# 42Board.net
KiCad netlist of a schematic drawn in EAGLE
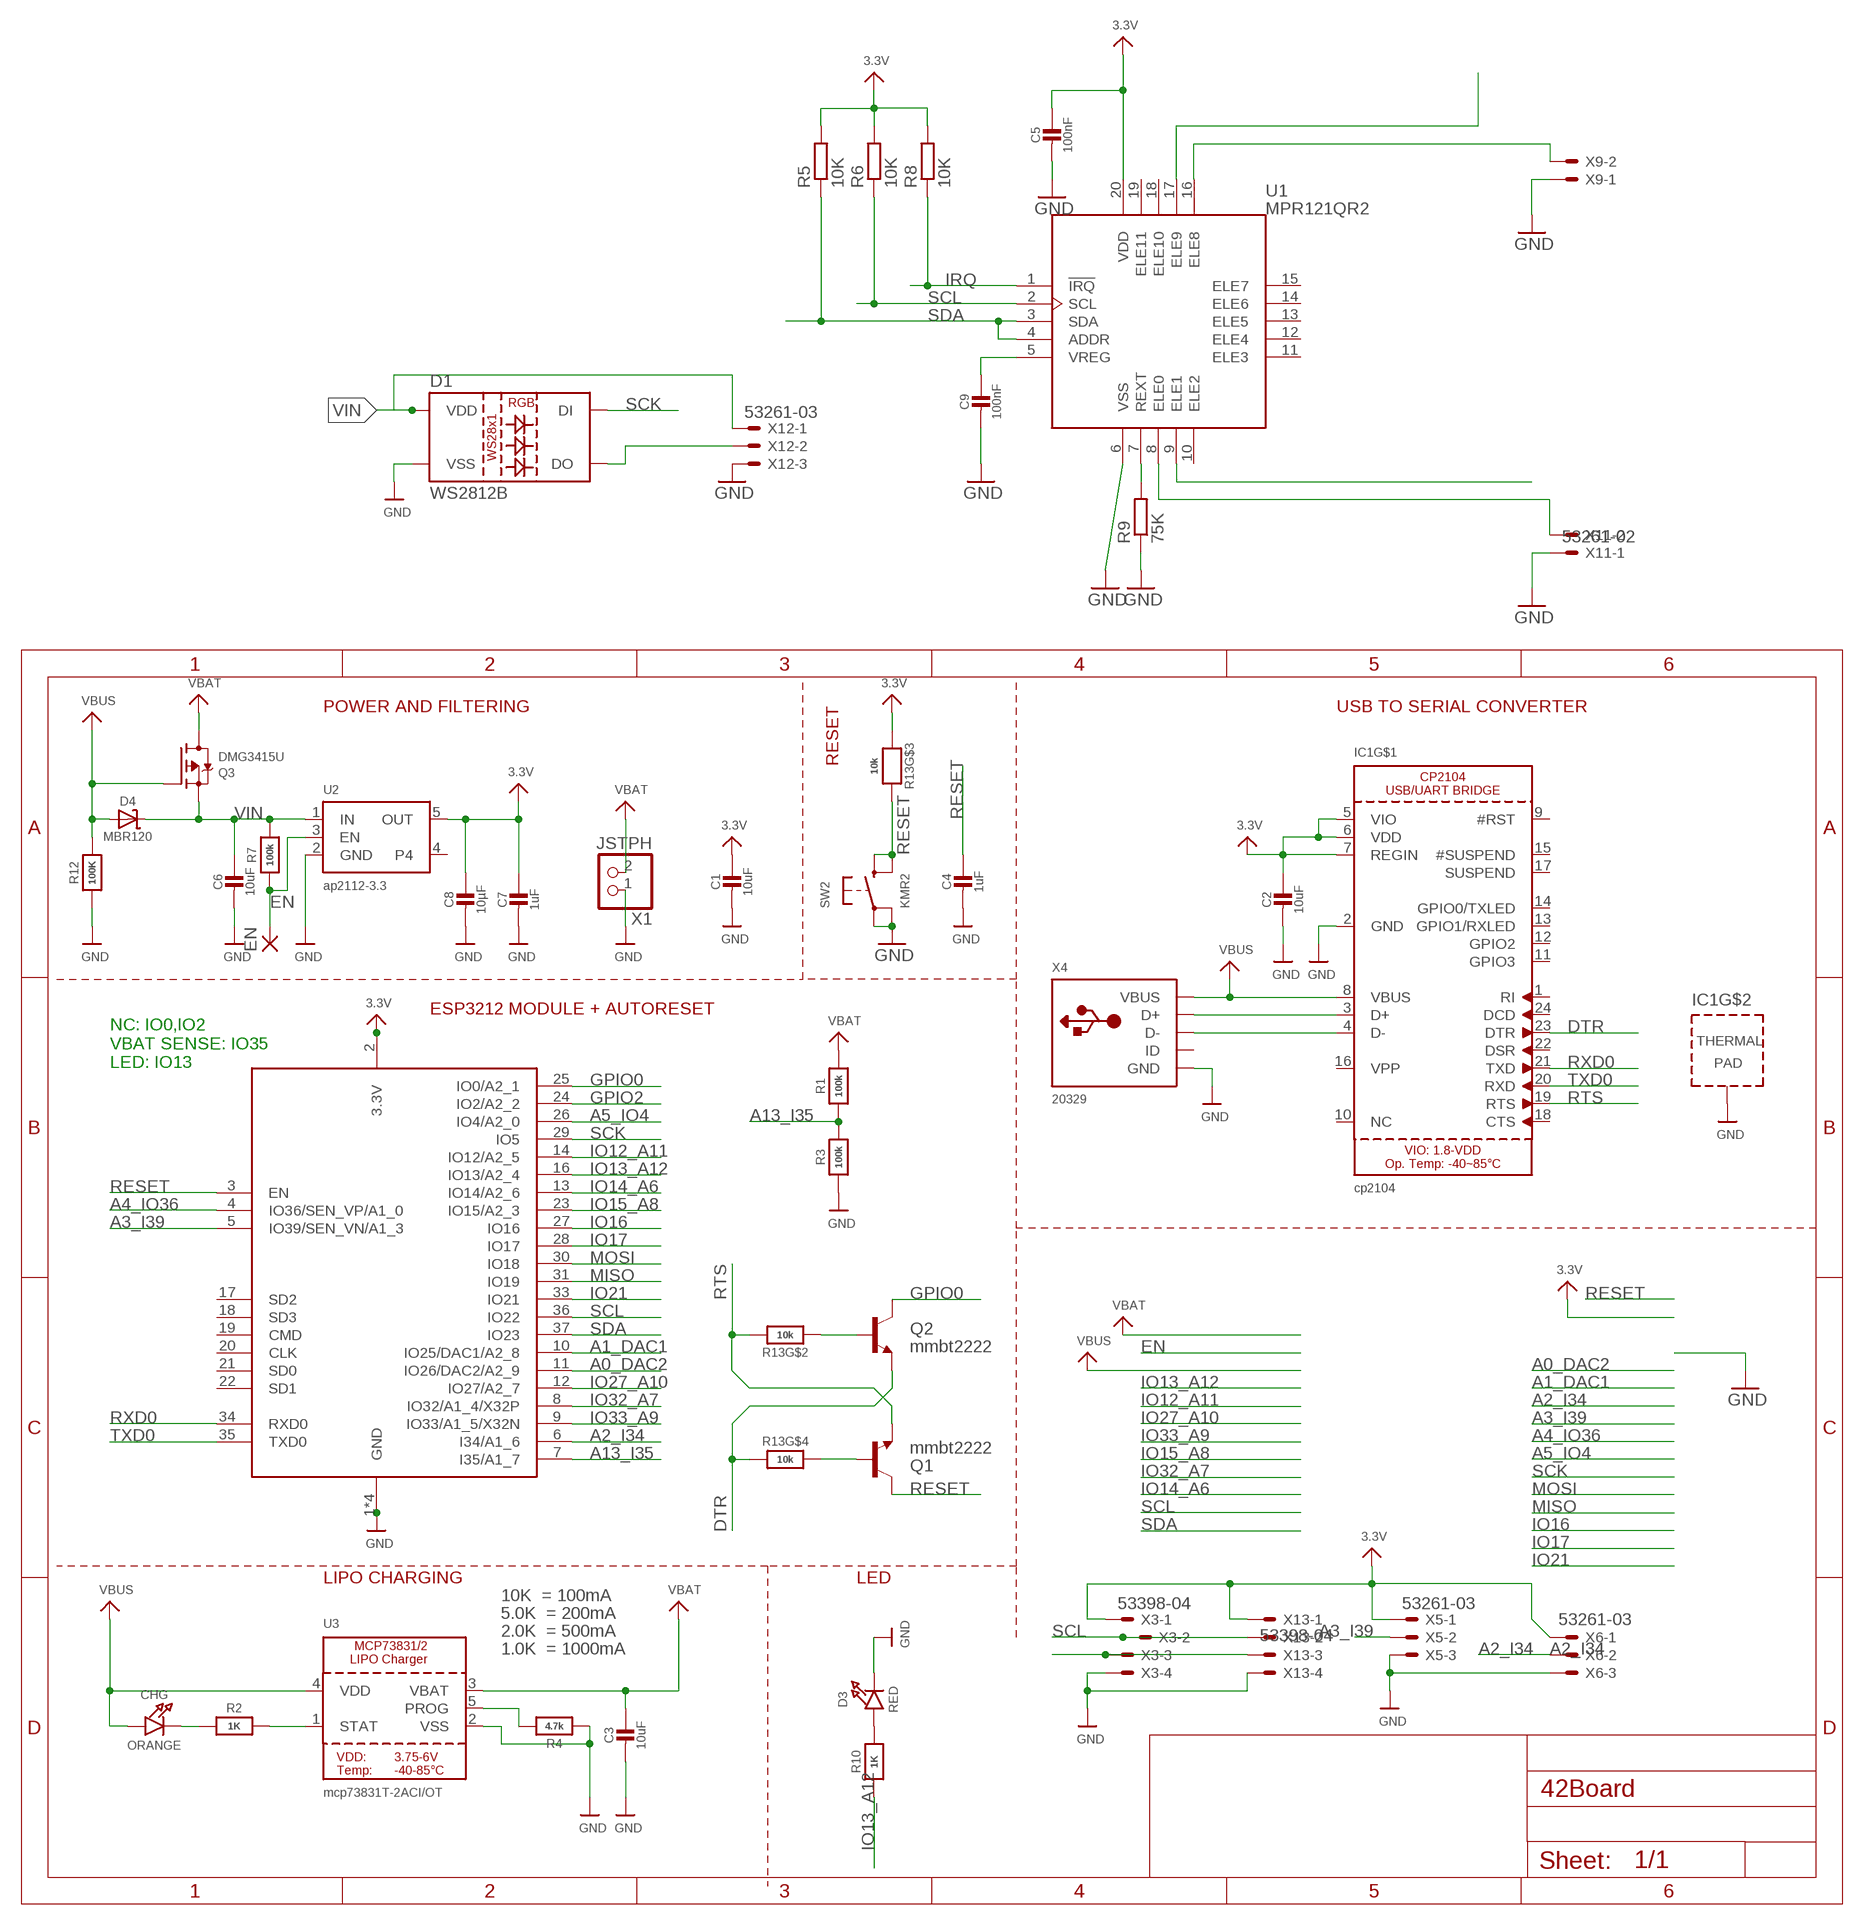
[diagram p0: schematic, sheet 1]

(export (version "E")
  (design (tool "Eeschema 10.0.6"))
  (components
    (comp (ref "C1")
      (value "10uF")
      (footprint "eagle-import:0805-NO")
      (libsource (lib "eagle-import") (part "CAP_CERAMIC0805-NOOUTLINE"))
    )
    (comp (ref "C2")
      (value "10uF")
      (footprint "eagle-import:0805-NO")
      (libsource (lib "eagle-import") (part "CAP_CERAMIC0805-NOOUTLINE"))
    )
    (comp (ref "C3")
      (value "10uF")
      (footprint "eagle-import:0805-NO")
      (libsource (lib "eagle-import") (part "CAP_CERAMIC0805-NOOUTLINE"))
    )
    (comp (ref "C4")
      (value "1uF")
      (footprint "eagle-import:0603-NO")
      (libsource (lib "eagle-import") (part "CAP_CERAMIC0603_NO"))
    )
    (comp (ref "C5")
      (value "100nF")
      (footprint "eagle-import:0603-NO")
      (libsource (lib "eagle-import") (part "CAP_CERAMIC0603_NO"))
    )
    (comp (ref "C6")
      (value "10uF")
      (footprint "eagle-import:0805-NO")
      (libsource (lib "eagle-import") (part "CAP_CERAMIC0805-NOOUTLINE"))
    )
    (comp (ref "C7")
      (value "1uF")
      (footprint "eagle-import:0603-NO")
      (libsource (lib "eagle-import") (part "CAP_CERAMIC0603_NO"))
    )
    (comp (ref "C8")
      (value "10µF")
      (footprint "eagle-import:0805-NO")
      (libsource (lib "eagle-import") (part "CAP_CERAMIC0805-NOOUTLINE"))
    )
    (comp (ref "C9")
      (value "100nF")
      (footprint "eagle-import:0603-NO")
      (libsource (lib "eagle-import") (part "CAP_CERAMIC0603_NO"))
    )
    (comp (ref "CHG")
      (value "ORANGE")
      (footprint "eagle-import:CHIPLED_0805_NOOUTLINE")
      (libsource (lib "eagle-import") (part "LED0805_NOOUTLINE"))
    )
    (comp (ref "D1")
      (value "WS2812B")
      (footprint "eagle-import:WS2812B")
      (libsource (lib "eagle-import") (part "WS2812B"))
    )
    (comp (ref "D3")
      (value "RED")
      (footprint "eagle-import:CHIPLED_0805_NOOUTLINE")
      (libsource (lib "eagle-import") (part "LED0805_NOOUTLINE"))
    )
    (comp (ref "D4")
      (value "MBR120")
      (footprint "eagle-import:SOD-123")
      (libsource (lib "eagle-import") (part "DIODE-SCHOTTKYSOD-123"))
    )
    (comp (ref "EN")
      (value "1,6/0,8")
      (footprint "eagle-import:1,6_0,8")
      (libsource (lib "eagle-import") (part "1,6/0,8"))
    )
    (comp (ref "IC1")
      (value "cp2104")
      (footprint "eagle-import:QFN24_4MM_SMSC")
      (libsource (lib "eagle-import") (part "CP2104"))
    )
    (comp (ref "Q1")
      (value "mmbt2222")
      (footprint "eagle-import:SOT23-3")
      (libsource (lib "eagle-import") (part "TRANSISTOR_NPNSOT23-3"))
    )
    (comp (ref "Q2")
      (value "mmbt2222")
      (footprint "eagle-import:SOT23-3")
      (libsource (lib "eagle-import") (part "TRANSISTOR_NPNSOT23-3"))
    )
    (comp (ref "Q3")
      (value "DMG3415U")
      (footprint "eagle-import:SOT23-R")
      (libsource (lib "eagle-import") (part "MOSFET-P"))
    )
    (comp (ref "R1")
      (value "100k")
      (footprint "eagle-import:0603-NO")
      (libsource (lib "eagle-import") (part "RESISTOR_0603_NOOUT"))
    )
    (comp (ref "R2")
      (value "1K")
      (footprint "eagle-import:0603-NO")
      (libsource (lib "eagle-import") (part "RESISTOR_0603_NOOUT"))
    )
    (comp (ref "R3")
      (value "100k")
      (footprint "eagle-import:0603-NO")
      (libsource (lib "eagle-import") (part "RESISTOR_0603_NOOUT"))
    )
    (comp (ref "R4")
      (value "4.7k")
      (footprint "eagle-import:0603-NO")
      (libsource (lib "eagle-import") (part "RESISTOR_0603_NOOUT"))
    )
    (comp (ref "R5")
      (value "10K")
      (footprint "eagle-import:R0603")
      (libsource (lib "eagle-import") (part "R-EU_R0603"))
    )
    (comp (ref "R6")
      (value "10K")
      (footprint "eagle-import:R0603")
      (libsource (lib "eagle-import") (part "R-EU_R0603"))
    )
    (comp (ref "R7")
      (value "100k")
      (footprint "eagle-import:0603-NO")
      (libsource (lib "eagle-import") (part "RESISTOR_0603_NOOUT"))
    )
    (comp (ref "R8")
      (value "10K")
      (footprint "eagle-import:R0603")
      (libsource (lib "eagle-import") (part "R-EU_R0603"))
    )
    (comp (ref "R9")
      (value "75K")
      (footprint "eagle-import:R0603")
      (libsource (lib "eagle-import") (part "R-EU_R0603"))
    )
    (comp (ref "R10")
      (value "1K")
      (footprint "eagle-import:0603-NO")
      (libsource (lib "eagle-import") (part "RESISTOR_0603_NOOUT"))
    )
    (comp (ref "R12")
      (value "100K")
      (footprint "eagle-import:0603-NO")
      (libsource (lib "eagle-import") (part "RESISTOR_0603_NOOUT"))
    )
    (comp (ref "R13")
      (value "10k")
      (footprint "eagle-import:RESPACK_4X0603")
      (libsource (lib "eagle-import") (part "RESISTOR_4PACK"))
    )
    (comp (ref "SW2")
      (value "KMR2")
      (footprint "eagle-import:BTN_KMR2_4.6X2.8")
      (libsource (lib "eagle-import") (part "SWITCH_TACT_SMT4.6X2.8"))
    )
    (comp (ref "U1")
      (value "MPR121QR2")
      (footprint "eagle-import:UFQFN-20")
      (fields
        (field (name "DIGI_KEY_PART_NUMBER") "MPR121QR2TR-ND")
        (field (name "MANUFACTURER") "NXP USA Inc.")
        (field (name "CREATED_BY") "PCBLayout.com")
      )
      (libsource (lib "eagle-import") (part "MPR121QR2"))
    )
    (comp (ref "U2")
      (value "ap2112-3.3")
      (footprint "eagle-import:SOT23-5")
      (libsource (lib "eagle-import") (part "VREG_SOT23-5"))
    )
    (comp (ref "U3")
      (value "mcp73831T-2ACI/OT")
      (footprint "eagle-import:SOT23-5")
      (libsource (lib "eagle-import") (part "MCP73831/2"))
    )
    (comp (ref "X1")
      (value "JSTPH")
      (footprint "eagle-import:JSTPH2")
      (libsource (lib "eagle-import") (part "CON_JST_PH_2PIN"))
    )
    (comp (ref "X2")
      (value "ESP32_WROOM32_SKINNY")
      (footprint "eagle-import:WROOM32_SKINNY")
      (libsource (lib "eagle-import") (part "ESP32_WROOM32_SKINNY"))
    )
    (comp (ref "X3")
      (value "53398-04")
      (footprint "eagle-import:53398-04")
      (fields (field (name "MF") "MOLEX"))
      (libsource (lib "eagle-import") (part "53?-04398"))
    )
    (comp (ref "X4")
      (value "20329")
      (footprint "eagle-import:4UCONN_20329_V2")
      (libsource (lib "eagle-import") (part "USB_MICRO_20329_V2"))
    )
    (comp (ref "X5")
      (value "53261-03")
      (footprint "eagle-import:53261-03")
      (fields (field (name "MF") "MOLEX") (field (name "MPN") "53261-0390"))
      (libsource (lib "eagle-import") (part "53?-03261"))
    )
    (comp (ref "X6")
      (value "53261-03")
      (footprint "eagle-import:53261-03")
      (fields (field (name "MF") "MOLEX") (field (name "MPN") "53261-0390"))
      (libsource (lib "eagle-import") (part "53?-03261"))
    )
    (comp (ref "X9")
      (value "53261-02")
      (footprint "eagle-import:53261-02")
      (fields (field (name "MF") "MOLEX"))
      (libsource (lib "eagle-import") (part "53?-02261"))
    )
    (comp (ref "X11")
      (value "53261-02")
      (footprint "eagle-import:53261-02")
      (fields (field (name "MF") "MOLEX"))
      (libsource (lib "eagle-import") (part "53?-02261"))
    )
    (comp (ref "X12")
      (value "53261-03")
      (footprint "eagle-import:53261-03")
      (fields (field (name "MF") "MOLEX") (field (name "MPN") "53261-0390"))
      (libsource (lib "eagle-import") (part "53?-03261"))
    )
    (comp (ref "X13")
      (value "53398-04")
      (footprint "eagle-import:53398-04")
      (fields (field (name "MF") "MOLEX"))
      (libsource (lib "eagle-import") (part "53?-04398"))
    )
  )
  (nets
    (net (code "1") (name "/A0_DAC2") (class "Default")
      (node (ref "X2") (pin "11") (pinfunction "IO26/DAC2/A2_9_11") (pintype "bidirectional"))
    )
    (net (code "2") (name "/A1_DAC1") (class "Default")
      (node (ref "X2") (pin "10") (pinfunction "IO25/DAC1/A2_8_10") (pintype "bidirectional"))
    )
    (net (code "3") (name "/A2_I34") (class "Default")
      (node (ref "X2") (pin "6") (pinfunction "I34/A1_6_6") (pintype "bidirectional"))
      (node (ref "X6") (pin "2") (pinfunction "S_2") (pintype "passive"))
    )
    (net (code "4") (name "/A3_I39") (class "Default")
      (node (ref "X2") (pin "5") (pinfunction "IO39/SEN_VN/A1_3_5") (pintype "passive"))
      (node (ref "X5") (pin "2") (pinfunction "S_2") (pintype "passive"))
    )
    (net (code "5") (name "/A4_IO36") (class "Default")
      (node (ref "X2") (pin "4") (pinfunction "IO36/SEN_VP/A1_0_4") (pintype "passive"))
    )
    (net (code "6") (name "/A5_IO4") (class "Default")
      (node (ref "X2") (pin "26") (pinfunction "IO4/A2_0_26") (pintype "bidirectional"))
    )
    (net (code "7") (name "/A13_I35") (class "Default")
      (node (ref "R1") (pin "1") (pinfunction "1_1") (pintype "passive"))
      (node (ref "R3") (pin "2") (pinfunction "2_2") (pintype "passive"))
      (node (ref "X2") (pin "7") (pinfunction "I35/A1_7_7") (pintype "bidirectional"))
    )
    (net (code "8") (name "/DTR") (class "Default")
      (node (ref "IC1") (pin "23") (pinfunction "DTR_23") (pintype "output"))
      (node (ref "Q2") (pin "2") (pinfunction "E_2") (pintype "passive"))
      (node (ref "R13") (pin "4") (pinfunction "1_4") (pintype "passive"))
    )
    (net (code "9") (name "/EN") (class "Default")
      (node (ref "EN") (pin "1") (pinfunction "P_1") (pintype "passive"))
      (node (ref "R7") (pin "1") (pinfunction "1_1") (pintype "passive"))
      (node (ref "U2") (pin "3") (pinfunction "EN_3") (pintype "input"))
    )
    (net (code "10") (name "/GPIO0") (class "Default")
      (node (ref "Q2") (pin "3") (pinfunction "C_3") (pintype "passive"))
      (node (ref "X2") (pin "25") (pinfunction "IO0/A2_1_25") (pintype "bidirectional"))
    )
    (net (code "11") (name "/GPIO2") (class "Default")
      (node (ref "X2") (pin "24") (pinfunction "IO2/A2_2_24") (pintype "bidirectional"))
    )
    (net (code "12") (name "/IO12_A11") (class "Default")
      (node (ref "X2") (pin "14") (pinfunction "IO12/A2_5_14") (pintype "bidirectional"))
    )
    (net (code "13") (name "/IO13_A12") (class "Default")
      (node (ref "R10") (pin "1") (pinfunction "1_1") (pintype "passive"))
      (node (ref "X2") (pin "16") (pinfunction "IO13/A2_4_16") (pintype "bidirectional"))
    )
    (net (code "14") (name "/IO14_A6") (class "Default")
      (node (ref "X2") (pin "13") (pinfunction "IO14/A2_6_13") (pintype "bidirectional"))
    )
    (net (code "15") (name "/IO15_A8") (class "Default")
      (node (ref "X2") (pin "23") (pinfunction "IO15/A2_3_23") (pintype "bidirectional"))
    )
    (net (code "16") (name "/IO16") (class "Default")
      (node (ref "X2") (pin "27") (pinfunction "IO16_27") (pintype "bidirectional"))
    )
    (net (code "17") (name "/IO17") (class "Default")
      (node (ref "X2") (pin "28") (pinfunction "IO17_28") (pintype "bidirectional"))
    )
    (net (code "18") (name "/IO21") (class "Default")
      (node (ref "X2") (pin "33") (pinfunction "IO21_33") (pintype "bidirectional"))
    )
    (net (code "19") (name "/IO27_A10") (class "Default")
      (node (ref "X2") (pin "12") (pinfunction "IO27/A2_7_12") (pintype "bidirectional"))
    )
    (net (code "20") (name "/IO32_A7") (class "Default")
      (node (ref "X2") (pin "8") (pinfunction "IO32/A1_4/X32P_8") (pintype "bidirectional"))
    )
    (net (code "21") (name "/IO33_A9") (class "Default")
      (node (ref "X2") (pin "9") (pinfunction "IO33/A1_5/X32N_9") (pintype "bidirectional"))
    )
    (net (code "22") (name "/IRQ") (class "Default")
      (node (ref "R8") (pin "1") (pinfunction "1_1") (pintype "passive"))
      (node (ref "U1") (pin "1") (pinfunction "~{IRQ}_1") (pintype "output"))
    )
    (net (code "23") (name "/MISO") (class "Default")
      (node (ref "X2") (pin "31") (pinfunction "IO19_31") (pintype "bidirectional"))
    )
    (net (code "24") (name "/MOSI") (class "Default")
      (node (ref "X2") (pin "30") (pinfunction "IO18_30") (pintype "bidirectional"))
    )
    (net (code "25") (name "/RESET") (class "Default")
      (node (ref "C4") (pin "1") (pinfunction "1_1") (pintype "passive"))
      (node (ref "Q1") (pin "3") (pinfunction "C_3") (pintype "passive"))
      (node (ref "R13") (pin "6") (pinfunction "2_6") (pintype "passive"))
      (node (ref "SW2") (pin "B") (pinfunction "S_B") (pintype "passive"))
      (node (ref "SW2") (pin "B'") (pinfunction "S1_B'") (pintype "passive"))
      (node (ref "X2") (pin "3") (pinfunction "EN_3") (pintype "input"))
    )
    (net (code "26") (name "/RTS") (class "Default")
      (node (ref "IC1") (pin "19") (pinfunction "RTS_19") (pintype "output"))
      (node (ref "Q1") (pin "2") (pinfunction "E_2") (pintype "passive"))
      (node (ref "R13") (pin "7") (pinfunction "2_7") (pintype "passive"))
    )
    (net (code "27") (name "/RXD0") (class "Default")
      (node (ref "IC1") (pin "21") (pinfunction "TXD_21") (pintype "output"))
      (node (ref "X2") (pin "34") (pinfunction "RXD0_34") (pintype "input"))
    )
    (net (code "28") (name "/SCK") (class "Default")
      (node (ref "D1") (pin "4") (pinfunction "DI_4") (pintype "bidirectional"))
      (node (ref "X2") (pin "29") (pinfunction "IO5_29") (pintype "bidirectional"))
    )
    (net (code "29") (name "/SCL") (class "Default")
      (node (ref "R6") (pin "1") (pinfunction "1_1") (pintype "passive"))
      (node (ref "U1") (pin "2") (pinfunction "SCL_2") (pintype "bidirectional"))
      (node (ref "X13") (pin "2") (pinfunction "S_2") (pintype "passive"))
      (node (ref "X2") (pin "36") (pinfunction "IO22_36") (pintype "bidirectional"))
      (node (ref "X3") (pin "2") (pinfunction "S_2") (pintype "passive"))
    )
    (net (code "30") (name "/SDA") (class "Default")
      (node (ref "R5") (pin "1") (pinfunction "1_1") (pintype "passive"))
      (node (ref "U1") (pin "3") (pinfunction "SDA_3") (pintype "passive"))
      (node (ref "U1") (pin "4") (pinfunction "ADDR_4") (pintype "input"))
      (node (ref "X13") (pin "3") (pinfunction "S_3") (pintype "passive"))
      (node (ref "X2") (pin "37") (pinfunction "IO23_37") (pintype "bidirectional"))
      (node (ref "X3") (pin "3") (pinfunction "S_3") (pintype "passive"))
    )
    (net (code "31") (name "/TXD0") (class "Default")
      (node (ref "IC1") (pin "20") (pinfunction "RXD_20") (pintype "input"))
      (node (ref "X2") (pin "35") (pinfunction "TXD0_35") (pintype "output"))
    )
    (net (code "32") (name "3.3V") (class "Default")
      (node (ref "C1") (pin "1") (pinfunction "1_1") (pintype "passive"))
      (node (ref "C2") (pin "1") (pinfunction "1_1") (pintype "passive"))
      (node (ref "C5") (pin "1") (pinfunction "1_1") (pintype "passive"))
      (node (ref "C7") (pin "1") (pinfunction "1_1") (pintype "passive"))
      (node (ref "C8") (pin "1") (pinfunction "1_1") (pintype "passive"))
      (node (ref "IC1") (pin "5") (pinfunction "VIO_5") (pintype "power_in"))
      (node (ref "IC1") (pin "6") (pinfunction "VDD_6") (pintype "power_in"))
      (node (ref "IC1") (pin "7") (pinfunction "REGIN_7") (pintype "power_in"))
      (node (ref "R13") (pin "3") (pinfunction "1_3") (pintype "passive"))
      (node (ref "R5") (pin "2") (pinfunction "2_2") (pintype "passive"))
      (node (ref "R6") (pin "2") (pinfunction "2_2") (pintype "passive"))
      (node (ref "R8") (pin "2") (pinfunction "2_2") (pintype "passive"))
      (node (ref "U1") (pin "20") (pinfunction "VDD_20") (pintype "power_in"))
      (node (ref "U2") (pin "5") (pinfunction "OUT_5") (pintype "power_in"))
      (node (ref "X13") (pin "1") (pinfunction "S_1") (pintype "passive"))
      (node (ref "X2") (pin "2") (pinfunction "3.3V_2") (pintype "passive"))
      (node (ref "X3") (pin "1") (pinfunction "S_1") (pintype "passive"))
      (node (ref "X5") (pin "1") (pinfunction "S_1") (pintype "passive"))
      (node (ref "X6") (pin "1") (pinfunction "S_1") (pintype "passive"))
    )
    (net (code "33") (name "GND") (class "Default")
      (node (ref "C1") (pin "2") (pinfunction "2_2") (pintype "passive"))
      (node (ref "C2") (pin "2") (pinfunction "2_2") (pintype "passive"))
      (node (ref "C3") (pin "2") (pinfunction "2_2") (pintype "passive"))
      (node (ref "C4") (pin "2") (pinfunction "2_2") (pintype "passive"))
      (node (ref "C5") (pin "2") (pinfunction "2_2") (pintype "passive"))
      (node (ref "C6") (pin "2") (pinfunction "2_2") (pintype "passive"))
      (node (ref "C7") (pin "2") (pinfunction "2_2") (pintype "passive"))
      (node (ref "C8") (pin "2") (pinfunction "2_2") (pintype "passive"))
      (node (ref "C9") (pin "2") (pinfunction "2_2") (pintype "passive"))
      (node (ref "D1") (pin "3") (pinfunction "VSS_3") (pintype "bidirectional"))
      (node (ref "D3") (pin "C") (pinfunction "C_C") (pintype "passive"))
      (node (ref "IC1") (pin "2") (pinfunction "GND_2") (pintype "power_in"))
      (node (ref "IC1") (pin "THERM") (pinfunction "TP_THERM") (pintype "power_in"))
      (node (ref "R12") (pin "1") (pinfunction "1_1") (pintype "passive"))
      (node (ref "R3") (pin "1") (pinfunction "1_1") (pintype "passive"))
      (node (ref "R4") (pin "1") (pinfunction "1_1") (pintype "passive"))
      (node (ref "R9") (pin "1") (pinfunction "1_1") (pintype "passive"))
      (node (ref "SW2") (pin "A") (pinfunction "P_A") (pintype "passive"))
      (node (ref "SW2") (pin "A'") (pinfunction "P1_A'") (pintype "passive"))
      (node (ref "U1") (pin "6") (pinfunction "VSS_6") (pintype "power_in"))
      (node (ref "U2") (pin "2") (pinfunction "GND_2") (pintype "power_in"))
      (node (ref "U3") (pin "2") (pinfunction "VSS_2") (pintype "power_in"))
      (node (ref "X1") (pin "1") (pinfunction "1_1") (pintype "passive"))
      (node (ref "X11") (pin "1") (pinfunction "S_1") (pintype "passive"))
      (node (ref "X12") (pin "3") (pinfunction "S_3") (pintype "passive"))
      (node (ref "X13") (pin "4") (pinfunction "S_4") (pintype "passive"))
      (node (ref "X2") (pin "1") (pinfunction "GND_1") (pintype "passive"))
      (node (ref "X2") (pin "15") (pinfunction "GND_15") (pintype "passive"))
      (node (ref "X2") (pin "38") (pinfunction "GND_38") (pintype "passive"))
      (node (ref "X2") (pin "P$1") (pinfunction "GND_P$1") (pintype "passive"))
      (node (ref "X3") (pin "4") (pinfunction "S_4") (pintype "passive"))
      (node (ref "X4") (pin "BASE@1") (pinfunction "GND_BASE@1") (pintype "power_in"))
      (node (ref "X4") (pin "BASE@2") (pinfunction "GND_BASE@2") (pintype "power_in"))
      (node (ref "X4") (pin "GND") (pinfunction "GND_GND") (pintype "power_in"))
      (node (ref "X4") (pin "SPRT@1") (pinfunction "GND_SPRT@1") (pintype "power_in"))
      (node (ref "X4") (pin "SPRT@2") (pinfunction "GND_SPRT@2") (pintype "power_in"))
      (node (ref "X4") (pin "SPRT@3") (pinfunction "GND_SPRT@3") (pintype "power_in"))
      (node (ref "X4") (pin "SPRT@4") (pinfunction "GND_SPRT@4") (pintype "power_in"))
      (node (ref "X5") (pin "3") (pinfunction "S_3") (pintype "passive"))
      (node (ref "X6") (pin "3") (pinfunction "S_3") (pintype "passive"))
      (node (ref "X9") (pin "1") (pinfunction "S_1") (pintype "passive"))
    )
    (net (code "34") (name "Net-(CHG-PadC)") (class "Default")
      (node (ref "CHG") (pin "C") (pinfunction "C_C") (pintype "passive"))
      (node (ref "R2") (pin "1") (pinfunction "1_1") (pintype "passive"))
    )
    (net (code "35") (name "Net-(D1-DO)") (class "Default")
      (node (ref "D1") (pin "2") (pinfunction "DO_2") (pintype "bidirectional"))
      (node (ref "X12") (pin "2") (pinfunction "S_2") (pintype "passive"))
    )
    (net (code "36") (name "Net-(D3-PadA)") (class "Default")
      (node (ref "D3") (pin "A") (pinfunction "A_A") (pintype "passive"))
      (node (ref "R10") (pin "2") (pinfunction "2_2") (pintype "passive"))
    )
    (net (code "37") (name "Net-(IC1A-D+)") (class "Default")
      (node (ref "IC1") (pin "3") (pinfunction "D+_3") (pintype "bidirectional"))
      (node (ref "X4") (pin "D+") (pinfunction "D+_D+") (pintype "bidirectional"))
    )
    (net (code "38") (name "Net-(IC1A-D-)") (class "Default")
      (node (ref "IC1") (pin "4") (pinfunction "D-_4") (pintype "bidirectional"))
      (node (ref "X4") (pin "D-") (pinfunction "D-_D-") (pintype "bidirectional"))
    )
    (net (code "39") (name "Net-(Q1-B)") (class "Default")
      (node (ref "Q1") (pin "1") (pinfunction "B_1") (pintype "passive"))
      (node (ref "R13") (pin "5") (pinfunction "2_5") (pintype "passive"))
    )
    (net (code "40") (name "Net-(Q2-B)") (class "Default")
      (node (ref "Q2") (pin "1") (pinfunction "B_1") (pintype "passive"))
      (node (ref "R13") (pin "2") (pinfunction "1_2") (pintype "passive"))
    )
    (net (code "41") (name "Net-(U1-ELE0)") (class "Default")
      (node (ref "U1") (pin "8") (pinfunction "ELE0_8") (pintype "passive"))
      (node (ref "X11") (pin "2") (pinfunction "S_2") (pintype "passive"))
    )
    (net (code "42") (name "Net-(U1-ELE8)") (class "Default")
      (node (ref "U1") (pin "16") (pinfunction "ELE8_16") (pintype "passive"))
      (node (ref "X9") (pin "2") (pinfunction "S_2") (pintype "passive"))
    )
    (net (code "43") (name "Net-(U1-REXT)") (class "Default")
      (node (ref "R9") (pin "2") (pinfunction "2_2") (pintype "passive"))
      (node (ref "U1") (pin "7") (pinfunction "REXT_7") (pintype "passive"))
    )
    (net (code "44") (name "Net-(U1-VREG)") (class "Default")
      (node (ref "C9") (pin "1") (pinfunction "1_1") (pintype "passive"))
      (node (ref "U1") (pin "5") (pinfunction "VREG_5") (pintype "passive"))
    )
    (net (code "45") (name "Net-(U3-PROG)") (class "Default")
      (node (ref "R4") (pin "2") (pinfunction "2_2") (pintype "passive"))
      (node (ref "U3") (pin "5") (pinfunction "PROG_5") (pintype "input"))
    )
    (net (code "46") (name "Net-(U3-STAT)") (class "Default")
      (node (ref "R2") (pin "2") (pinfunction "2_2") (pintype "passive"))
      (node (ref "U3") (pin "1") (pinfunction "STAT_1") (pintype "output"))
    )
    (net (code "47") (name "VBAT") (class "Default")
      (node (ref "C3") (pin "1") (pinfunction "1_1") (pintype "passive"))
      (node (ref "Q3") (pin "3") (pinfunction "D_3") (pintype "passive"))
      (node (ref "R1") (pin "2") (pinfunction "2_2") (pintype "passive"))
      (node (ref "U3") (pin "3") (pinfunction "VBAT_3") (pintype "power_in"))
      (node (ref "X1") (pin "2") (pinfunction "2_2") (pintype "passive"))
    )
    (net (code "48") (name "VBUS") (class "Default")
      (node (ref "CHG") (pin "A") (pinfunction "A_A") (pintype "passive"))
      (node (ref "D4") (pin "A") (pinfunction "A_A") (pintype "passive"))
      (node (ref "IC1") (pin "8") (pinfunction "VBUS_8") (pintype "power_in"))
      (node (ref "Q3") (pin "1") (pinfunction "G_1") (pintype "passive"))
      (node (ref "R12") (pin "2") (pinfunction "2_2") (pintype "passive"))
      (node (ref "U3") (pin "4") (pinfunction "VDD_4") (pintype "power_in"))
      (node (ref "X4") (pin "VBUS") (pinfunction "VBUS_VBUS") (pintype "power_in"))
    )
    (net (code "49") (name "VIN") (class "Default")
      (node (ref "C6") (pin "1") (pinfunction "1_1") (pintype "passive"))
      (node (ref "D1") (pin "1") (pinfunction "VDD_1") (pintype "bidirectional"))
      (node (ref "D4") (pin "C") (pinfunction "C_C") (pintype "passive"))
      (node (ref "Q3") (pin "2") (pinfunction "S_2") (pintype "passive"))
      (node (ref "R7") (pin "2") (pinfunction "2_2") (pintype "passive"))
      (node (ref "U2") (pin "1") (pinfunction "IN_1") (pintype "power_in"))
      (node (ref "X12") (pin "1") (pinfunction "S_1") (pintype "passive"))
    )
    (net (code "50") (name "unconnected-(IC1A-#RST-Pad9)") (class "Default")
      (node (ref "IC1") (pin "9") (pinfunction "#RST_9") (pintype "bidirectional"))
    )
    (net (code "51") (name "unconnected-(IC1A-#SUSPEND-Pad15)") (class "Default")
      (node (ref "IC1") (pin "15") (pinfunction "#SUSPEND_15") (pintype "output"))
    )
    (net (code "52") (name "unconnected-(IC1A-CTS-Pad18)") (class "Default")
      (node (ref "IC1") (pin "18") (pinfunction "CTS_18") (pintype "input"))
    )
    (net (code "53") (name "unconnected-(IC1A-DCD-Pad24)") (class "Default")
      (node (ref "IC1") (pin "24") (pinfunction "DCD_24") (pintype "input"))
    )
    (net (code "54") (name "unconnected-(IC1A-DSR-Pad22)") (class "Default")
      (node (ref "IC1") (pin "22") (pinfunction "DSR_22") (pintype "input"))
    )
    (net (code "55") (name "unconnected-(IC1A-GPIO0{slash}TXLED-Pad14)") (class "Default")
      (node (ref "IC1") (pin "14") (pinfunction "GPIO0/TXLED_14") (pintype "bidirectional"))
    )
    (net (code "56") (name "unconnected-(IC1A-GPIO1{slash}RXLED-Pad13)") (class "Default")
      (node (ref "IC1") (pin "13") (pinfunction "GPIO1/RXLED_13") (pintype "bidirectional"))
    )
    (net (code "57") (name "unconnected-(IC1A-GPIO2-Pad12)") (class "Default")
      (node (ref "IC1") (pin "12") (pinfunction "GPIO2_12") (pintype "bidirectional"))
    )
    (net (code "58") (name "unconnected-(IC1A-GPIO3-Pad11)") (class "Default")
      (node (ref "IC1") (pin "11") (pinfunction "GPIO3_11") (pintype "bidirectional"))
    )
    (net (code "59") (name "unconnected-(IC1A-NC-Pad10)") (class "Default")
      (node (ref "IC1") (pin "10") (pinfunction "NC_10") (pintype "no_connect"))
    )
    (net (code "60") (name "unconnected-(IC1A-RI-Pad1)") (class "Default")
      (node (ref "IC1") (pin "1") (pinfunction "RI_1") (pintype "input"))
    )
    (net (code "61") (name "unconnected-(IC1A-SUSPEND-Pad17)") (class "Default")
      (node (ref "IC1") (pin "17") (pinfunction "SUSPEND_17") (pintype "output"))
    )
    (net (code "62") (name "unconnected-(IC1A-VPP-Pad16)") (class "Default")
      (node (ref "IC1") (pin "16") (pinfunction "VPP_16") (pintype "bidirectional"))
    )
    (net (code "63") (name "unconnected-(U1-ELE1-Pad9)") (class "Default")
      (node (ref "U1") (pin "9") (pinfunction "ELE1_9") (pintype "passive"))
    )
    (net (code "64") (name "unconnected-(U1-ELE2-Pad10)") (class "Default")
      (node (ref "U1") (pin "10") (pinfunction "ELE2_10") (pintype "passive"))
    )
    (net (code "65") (name "unconnected-(U1-ELE3-Pad11)") (class "Default")
      (node (ref "U1") (pin "11") (pinfunction "ELE3_11") (pintype "passive"))
    )
    (net (code "66") (name "unconnected-(U1-ELE4-Pad12)") (class "Default")
      (node (ref "U1") (pin "12") (pinfunction "ELE4_12") (pintype "passive"))
    )
    (net (code "67") (name "unconnected-(U1-ELE5-Pad13)") (class "Default")
      (node (ref "U1") (pin "13") (pinfunction "ELE5_13") (pintype "passive"))
    )
    (net (code "68") (name "unconnected-(U1-ELE6-Pad14)") (class "Default")
      (node (ref "U1") (pin "14") (pinfunction "ELE6_14") (pintype "passive"))
    )
    (net (code "69") (name "unconnected-(U1-ELE7-Pad15)") (class "Default")
      (node (ref "U1") (pin "15") (pinfunction "ELE7_15") (pintype "passive"))
    )
    (net (code "70") (name "unconnected-(U1-ELE9-Pad17)") (class "Default")
      (node (ref "U1") (pin "17") (pinfunction "ELE9_17") (pintype "passive"))
    )
    (net (code "71") (name "unconnected-(U1-ELE10-Pad18)") (class "Default")
      (node (ref "U1") (pin "18") (pinfunction "ELE10_18") (pintype "passive"))
    )
    (net (code "72") (name "unconnected-(U1-ELE11-Pad19)") (class "Default")
      (node (ref "U1") (pin "19") (pinfunction "ELE11_19") (pintype "passive"))
    )
    (net (code "73") (name "unconnected-(U2-P4-Pad4)") (class "Default")
      (node (ref "U2") (pin "4") (pinfunction "P4_4") (pintype "bidirectional"))
    )
    (net (code "74") (name "unconnected-(X2-CLK-Pad20)") (class "Default")
      (node (ref "X2") (pin "20") (pinfunction "CLK_20") (pintype "bidirectional"))
    )
    (net (code "75") (name "unconnected-(X2-CMD-Pad19)") (class "Default")
      (node (ref "X2") (pin "19") (pinfunction "CMD_19") (pintype "bidirectional"))
    )
    (net (code "76") (name "unconnected-(X2-SD0-Pad21)") (class "Default")
      (node (ref "X2") (pin "21") (pinfunction "SD0_21") (pintype "bidirectional"))
    )
    (net (code "77") (name "unconnected-(X2-SD1-Pad22)") (class "Default")
      (node (ref "X2") (pin "22") (pinfunction "SD1_22") (pintype "bidirectional"))
    )
    (net (code "78") (name "unconnected-(X2-SD2-Pad17)") (class "Default")
      (node (ref "X2") (pin "17") (pinfunction "SD2_17") (pintype "bidirectional"))
    )
    (net (code "79") (name "unconnected-(X2-SD3-Pad18)") (class "Default")
      (node (ref "X2") (pin "18") (pinfunction "SD3_18") (pintype "bidirectional"))
    )
    (net (code "80") (name "unconnected-(X4-PadID)") (class "Default")
      (node (ref "X4") (pin "ID") (pinfunction "ID_ID") (pintype "bidirectional"))
    )
  )
)
